# VALVEBOARD_Isolation.net
KiCad netlist of a schematic drawn in Altium Designer
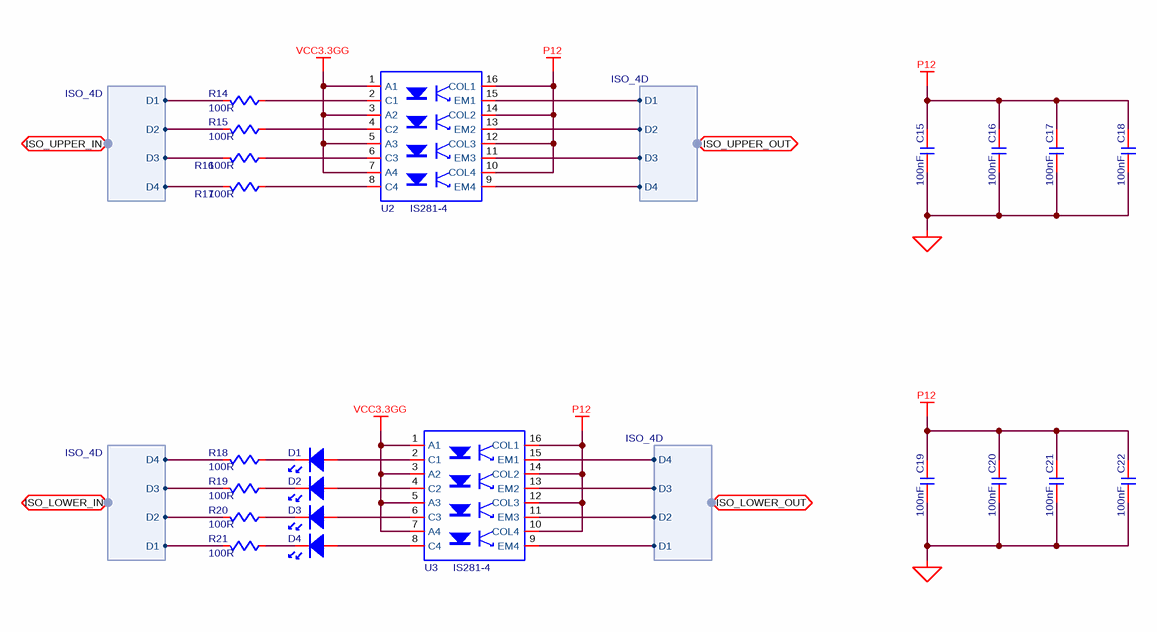
[diagram p0: VALVEBOARD_Isolation.SchDoc]

(export (version "E")
  (design (tool "Eeschema 10.0.6"))
  (components
    (comp (ref "C15")
      (value "100nF")
      (footprint "zynq:C0603")
      (fields (field (name "VOLTAGE") "25V") (field (name "Comment") "C-NOMO"))
      (libsource (lib "zynq") (part "C-NOMO"))
    )
    (comp (ref "C16")
      (value "100nF")
      (footprint "zynq:C0603")
      (fields (field (name "VOLTAGE") "25V") (field (name "Comment") "C-NOMO"))
      (libsource (lib "zynq") (part "C-NOMO"))
    )
    (comp (ref "C17")
      (value "100nF")
      (footprint "zynq:C0603")
      (fields (field (name "VOLTAGE") "25V") (field (name "Comment") "C-NOMO"))
      (libsource (lib "zynq") (part "C-NOMO"))
    )
    (comp (ref "C18")
      (value "100nF")
      (footprint "zynq:C0603")
      (fields (field (name "VOLTAGE") "25V") (field (name "Comment") "C-NOMO"))
      (libsource (lib "zynq") (part "C-NOMO"))
    )
    (comp (ref "C19")
      (value "100nF")
      (footprint "zynq:C0603")
      (fields (field (name "VOLTAGE") "25V") (field (name "Comment") "C-NOMO"))
      (libsource (lib "zynq") (part "C-NOMO"))
    )
    (comp (ref "C20")
      (value "100nF")
      (footprint "zynq:C0603")
      (fields (field (name "VOLTAGE") "25V") (field (name "Comment") "C-NOMO"))
      (libsource (lib "zynq") (part "C-NOMO"))
    )
    (comp (ref "C21")
      (value "100nF")
      (footprint "zynq:C0603")
      (fields (field (name "VOLTAGE") "25V") (field (name "Comment") "C-NOMO"))
      (libsource (lib "zynq") (part "C-NOMO"))
    )
    (comp (ref "C22")
      (value "100nF")
      (footprint "zynq:C0603")
      (fields (field (name "VOLTAGE") "25V") (field (name "Comment") "C-NOMO"))
      (libsource (lib "zynq") (part "C-NOMO"))
    )
    (comp (ref "D1") (value "LED") (footprint "zynq:LED0603") (libsource (lib "zynq") (part "LED")))
    (comp (ref "D2") (value "LED") (footprint "zynq:LED0603") (libsource (lib "zynq") (part "LED")))
    (comp (ref "D3") (value "LED") (footprint "zynq:LED0603") (libsource (lib "zynq") (part "LED")))
    (comp (ref "D4") (value "LED") (footprint "zynq:LED0603") (libsource (lib "zynq") (part "LED")))
    (comp (ref "R14")
      (value "100R")
      (footprint "zynq:R0603")
      (fields (field (name "Comment") "R"))
      (libsource (lib "zynq") (part "R"))
    )
    (comp (ref "R15")
      (value "100R")
      (footprint "zynq:R0603")
      (fields (field (name "Comment") "R"))
      (libsource (lib "zynq") (part "R"))
    )
    (comp (ref "R16")
      (value "100R")
      (footprint "zynq:R0603")
      (fields (field (name "Comment") "R"))
      (libsource (lib "zynq") (part "R"))
    )
    (comp (ref "R17")
      (value "100R")
      (footprint "zynq:R0603")
      (fields (field (name "Comment") "R"))
      (libsource (lib "zynq") (part "R"))
    )
    (comp (ref "R18")
      (value "100R")
      (footprint "zynq:R0603")
      (fields (field (name "Comment") "R"))
      (libsource (lib "zynq") (part "R"))
    )
    (comp (ref "R19")
      (value "100R")
      (footprint "zynq:R0603")
      (fields (field (name "Comment") "R"))
      (libsource (lib "zynq") (part "R"))
    )
    (comp (ref "R20")
      (value "100R")
      (footprint "zynq:R0603")
      (fields (field (name "Comment") "R"))
      (libsource (lib "zynq") (part "R"))
    )
    (comp (ref "R21")
      (value "100R")
      (footprint "zynq:R0603")
      (fields (field (name "Comment") "R"))
      (libsource (lib "zynq") (part "R"))
    )
    (comp (ref "U2") (value "IS281-4") (footprint "zynq:PS2801") (libsource (lib "zynq") (part "PS2801")))
    (comp (ref "U3") (value "IS281-4") (footprint "zynq:PS2801") (libsource (lib "zynq") (part "PS2801")))
  )
  (nets
    (net (code "3") (name "Net-(D1-Pad1)") (class "Default")
      (node (ref "D1") (pin "1") (pinfunction "1_1") (pintype "passive"))
      (node (ref "R18") (pin "2") (pinfunction "2_2") (pintype "passive"))
    )
    (net (code "4") (name "Net-(D2-Pad1)") (class "Default")
      (node (ref "D2") (pin "1") (pinfunction "1_1") (pintype "passive"))
      (node (ref "R19") (pin "2") (pinfunction "2_2") (pintype "passive"))
    )
    (net (code "5") (name "Net-(D3-Pad1)") (class "Default")
      (node (ref "D3") (pin "1") (pinfunction "1_1") (pintype "passive"))
      (node (ref "R20") (pin "2") (pinfunction "2_2") (pintype "passive"))
    )
    (net (code "6") (name "Net-(D4-Pad1)") (class "Default")
      (node (ref "D4") (pin "1") (pinfunction "1_1") (pintype "passive"))
      (node (ref "R21") (pin "2") (pinfunction "2_2") (pintype "passive"))
    )
    (net (code "7") (name "Net-(U2-C1)") (class "Default")
      (node (ref "R14") (pin "2") (pinfunction "2_2") (pintype "passive"))
      (node (ref "U2") (pin "2") (pinfunction "C1_2") (pintype "passive"))
    )
    (net (code "8") (name "Net-(U2-C2)") (class "Default")
      (node (ref "R15") (pin "2") (pinfunction "2_2") (pintype "passive"))
      (node (ref "U2") (pin "4") (pinfunction "C2_4") (pintype "passive"))
    )
    (net (code "9") (name "Net-(U2-C3)") (class "Default")
      (node (ref "R16") (pin "2") (pinfunction "2_2") (pintype "passive"))
      (node (ref "U2") (pin "6") (pinfunction "C3_6") (pintype "passive"))
    )
    (net (code "10") (name "Net-(U2-C4)") (class "Default")
      (node (ref "R17") (pin "2") (pinfunction "2_2") (pintype "passive"))
      (node (ref "U2") (pin "8") (pinfunction "C4_8") (pintype "passive"))
    )
    (net (code "11") (name "Net-(U3-C1)") (class "Default")
      (node (ref "D1") (pin "2") (pinfunction "2_2") (pintype "passive"))
      (node (ref "U3") (pin "2") (pinfunction "C1_2") (pintype "passive"))
    )
    (net (code "12") (name "Net-(U3-C2)") (class "Default")
      (node (ref "D2") (pin "2") (pinfunction "2_2") (pintype "passive"))
      (node (ref "U3") (pin "4") (pinfunction "C2_4") (pintype "passive"))
    )
    (net (code "13") (name "Net-(U3-C3)") (class "Default")
      (node (ref "D3") (pin "2") (pinfunction "2_2") (pintype "passive"))
      (node (ref "U3") (pin "6") (pinfunction "C3_6") (pintype "passive"))
    )
    (net (code "14") (name "Net-(U3-C4)") (class "Default")
      (node (ref "D4") (pin "2") (pinfunction "2_2") (pintype "passive"))
      (node (ref "U3") (pin "8") (pinfunction "C4_8") (pintype "passive"))
    )
    (net (code "15") (name "P12") (class "Default")
      (node (ref "C15") (pin "2") (pinfunction "2_2") (pintype "passive"))
      (node (ref "C16") (pin "2") (pinfunction "2_2") (pintype "passive"))
      (node (ref "C17") (pin "2") (pinfunction "2_2") (pintype "passive"))
      (node (ref "C18") (pin "2") (pinfunction "2_2") (pintype "passive"))
      (node (ref "C19") (pin "2") (pinfunction "2_2") (pintype "passive"))
      (node (ref "C20") (pin "2") (pinfunction "2_2") (pintype "passive"))
      (node (ref "C21") (pin "2") (pinfunction "2_2") (pintype "passive"))
      (node (ref "C22") (pin "2") (pinfunction "2_2") (pintype "passive"))
      (node (ref "U2") (pin "10") (pinfunction "COL4_10") (pintype "passive"))
      (node (ref "U2") (pin "12") (pinfunction "COL3_12") (pintype "passive"))
      (node (ref "U2") (pin "14") (pinfunction "COL2_14") (pintype "passive"))
      (node (ref "U2") (pin "16") (pinfunction "COL1_16") (pintype "passive"))
      (node (ref "U3") (pin "10") (pinfunction "COL4_10") (pintype "passive"))
      (node (ref "U3") (pin "12") (pinfunction "COL3_12") (pintype "passive"))
      (node (ref "U3") (pin "14") (pinfunction "COL2_14") (pintype "passive"))
      (node (ref "U3") (pin "16") (pinfunction "COL1_16") (pintype "passive"))
    )
    (net (code "16") (name "PGND") (class "Default")
      (node (ref "C15") (pin "1") (pinfunction "1_1") (pintype "passive"))
      (node (ref "C16") (pin "1") (pinfunction "1_1") (pintype "passive"))
      (node (ref "C17") (pin "1") (pinfunction "1_1") (pintype "passive"))
      (node (ref "C18") (pin "1") (pinfunction "1_1") (pintype "passive"))
      (node (ref "C19") (pin "1") (pinfunction "1_1") (pintype "passive"))
      (node (ref "C20") (pin "1") (pinfunction "1_1") (pintype "passive"))
      (node (ref "C21") (pin "1") (pinfunction "1_1") (pintype "passive"))
      (node (ref "C22") (pin "1") (pinfunction "1_1") (pintype "passive"))
    )
    (net (code "17") (name "VCC3.3GG") (class "Default")
      (node (ref "U2") (pin "1") (pinfunction "A1_1") (pintype "passive"))
      (node (ref "U2") (pin "3") (pinfunction "A2_3") (pintype "passive"))
      (node (ref "U2") (pin "5") (pinfunction "A3_5") (pintype "passive"))
      (node (ref "U2") (pin "7") (pinfunction "A4_7") (pintype "passive"))
      (node (ref "U3") (pin "1") (pinfunction "A1_1") (pintype "passive"))
      (node (ref "U3") (pin "3") (pinfunction "A2_3") (pintype "passive"))
      (node (ref "U3") (pin "5") (pinfunction "A3_5") (pintype "passive"))
      (node (ref "U3") (pin "7") (pinfunction "A4_7") (pintype "passive"))
    )
    (net (code "18") (name "unconnected-(R14-Pad1)") (class "Default")
      (node (ref "R14") (pin "1") (pinfunction "1_1") (pintype "passive"))
    )
    (net (code "19") (name "unconnected-(R15-Pad1)") (class "Default")
      (node (ref "R15") (pin "1") (pinfunction "1_1") (pintype "passive"))
    )
    (net (code "20") (name "unconnected-(R16-Pad1)") (class "Default")
      (node (ref "R16") (pin "1") (pinfunction "1_1") (pintype "passive"))
    )
    (net (code "21") (name "unconnected-(R17-Pad1)") (class "Default")
      (node (ref "R17") (pin "1") (pinfunction "1_1") (pintype "passive"))
    )
    (net (code "22") (name "unconnected-(R18-Pad1)") (class "Default")
      (node (ref "R18") (pin "1") (pinfunction "1_1") (pintype "passive"))
    )
    (net (code "23") (name "unconnected-(R19-Pad1)") (class "Default")
      (node (ref "R19") (pin "1") (pinfunction "1_1") (pintype "passive"))
    )
    (net (code "24") (name "unconnected-(R20-Pad1)") (class "Default")
      (node (ref "R20") (pin "1") (pinfunction "1_1") (pintype "passive"))
    )
    (net (code "25") (name "unconnected-(R21-Pad1)") (class "Default")
      (node (ref "R21") (pin "1") (pinfunction "1_1") (pintype "passive"))
    )
    (net (code "26") (name "unconnected-(U2-EM1-Pad15)") (class "Default")
      (node (ref "U2") (pin "15") (pinfunction "EM1_15") (pintype "passive"))
    )
    (net (code "27") (name "unconnected-(U2-EM2-Pad13)") (class "Default")
      (node (ref "U2") (pin "13") (pinfunction "EM2_13") (pintype "passive"))
    )
    (net (code "28") (name "unconnected-(U2-EM3-Pad11)") (class "Default")
      (node (ref "U2") (pin "11") (pinfunction "EM3_11") (pintype "passive"))
    )
    (net (code "29") (name "unconnected-(U2-EM4-Pad9)") (class "Default")
      (node (ref "U2") (pin "9") (pinfunction "EM4_9") (pintype "passive"))
    )
    (net (code "30") (name "unconnected-(U3-EM1-Pad15)") (class "Default")
      (node (ref "U3") (pin "15") (pinfunction "EM1_15") (pintype "passive"))
    )
    (net (code "31") (name "unconnected-(U3-EM2-Pad13)") (class "Default")
      (node (ref "U3") (pin "13") (pinfunction "EM2_13") (pintype "passive"))
    )
    (net (code "32") (name "unconnected-(U3-EM3-Pad11)") (class "Default")
      (node (ref "U3") (pin "11") (pinfunction "EM3_11") (pintype "passive"))
    )
    (net (code "33") (name "unconnected-(U3-EM4-Pad9)") (class "Default")
      (node (ref "U3") (pin "9") (pinfunction "EM4_9") (pintype "passive"))
    )
  )
)
